# A1-MAIN.net
KiCad netlist of a schematic drawn in Altium Designer
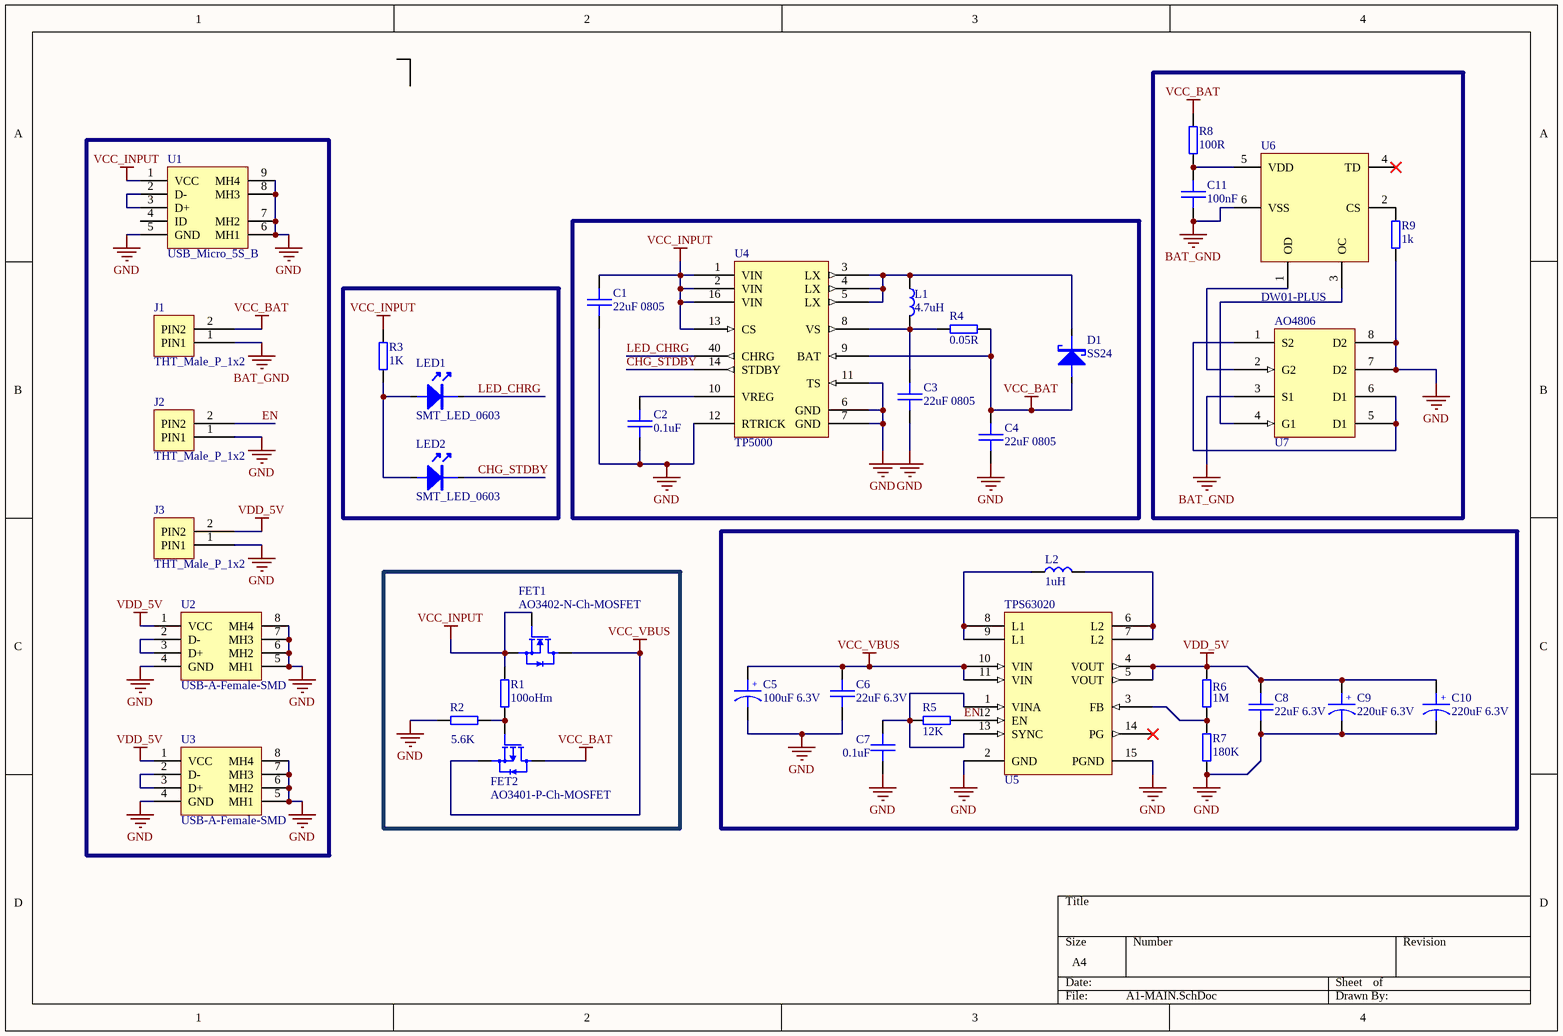
[diagram p0: A1-MAIN.SchDoc]

(export (version "E")
  (design (tool "Eeschema 10.0.6"))
  (components
    (comp (ref "AO4806") (value "U7") (footprint "SOP-8") (libsource (lib "电源管理") (part "AO4806")))
    (comp (ref "C1")
      (value "22uF 0805")
      (footprint "SMT_C_0805")
      (description "Surface mount capacitor 0805")
      (libsource (lib "Vowstar_Basic_Device") (part "SMT_C_0805"))
    )
    (comp (ref "C2")
      (value "0.1uF")
      (footprint "SMT_C_0603")
      (description "Surface mount capacitor 0603")
      (libsource (lib "Vowstar_Basic_Device") (part "SMT_C_0603"))
    )
    (comp (ref "C3")
      (value "22uF 0805")
      (footprint "SMT_C_0805")
      (description "Surface mount capacitor 0805")
      (libsource (lib "Vowstar_Basic_Device") (part "SMT_C_0805"))
    )
    (comp (ref "C4")
      (value "22uF 0805")
      (footprint "SMT_C_0805")
      (description "Surface mount capacitor 0805")
      (libsource (lib "Vowstar_Basic_Device") (part "SMT_C_0805"))
    )
    (comp (ref "C5")
      (value "100uF 6.3V")
      (footprint "SMT_C_Tantalum_A")
      (description "Capacitor, SM Tantalum; Body 3.2 x 1.6 mm (LxW typ)")
      (libsource (lib "Vowstar_Basic_Device") (part "SMT_C_Tantalum_A"))
    )
    (comp (ref "C6")
      (value "22uF 6.3V")
      (footprint "SMT_C_0805")
      (description "Surface mount capacitor 0805")
      (libsource (lib "Vowstar_Basic_Device") (part "SMT_C_0805"))
    )
    (comp (ref "C7")
      (value "0.1uF")
      (footprint "SMT_C_0603")
      (description "Surface mount capacitor 0603")
      (libsource (lib "Vowstar_Basic_Device") (part "SMT_C_0603"))
    )
    (comp (ref "C8")
      (value "22uF 6.3V")
      (footprint "SMT_C_0805")
      (description "Surface mount capacitor 0805")
      (libsource (lib "Vowstar_Basic_Device") (part "SMT_C_0805"))
    )
    (comp (ref "C9")
      (value "220uF 6.3V")
      (footprint "SMT_C_Tantalum_B")
      (description "Capacitor, SM Tantalum; Body 3.5 x 2.8 mm (LxW typ)")
      (libsource (lib "Vowstar_Basic_Device") (part "SMT_C_Tantalum_B"))
    )
    (comp (ref "C10")
      (value "220uF 6.3V")
      (footprint "SMT_C_Tantalum_B")
      (description "Capacitor, SM Tantalum; Body 3.5 x 2.8 mm (LxW typ)")
      (libsource (lib "Vowstar_Basic_Device") (part "SMT_C_Tantalum_B"))
    )
    (comp (ref "C11")
      (value "100nF")
      (footprint "SMT_C_0603")
      (description "Surface mount capacitor 0603")
      (libsource (lib "Vowstar_Basic_Device") (part "SMT_C_0603"))
    )
    (comp (ref "D1")
      (value "SS24")
      (footprint "SMT_DIODE_DO_214AC")
      (description "Surface mount schottky diode DO-214AC(SMA) Package")
      (libsource (lib "Vowstar_Basic_Device") (part "SMT_DIODE_SCHOTTKY_DO_214AC"))
    )
    (comp (ref "FET1")
      (value "AO3402-N-Ch-MOSFET")
      (footprint "AO3402-N-Ch-MOSFET")
      (description "AO3402-N-Ch,4A,30V.RDS(ON) = 0.11Ω @ VGS = 2.5V")
      (libsource (lib "Vowstar_Basic_Device") (part "AO3402-N-Ch-MOSFET"))
    )
    (comp (ref "FET2")
      (value "AO3401-P-Ch-MOSFET")
      (footprint "AO3401-P-Ch-MOSFET")
      (description "AO3401-P-Ch,-4.2A, -30V.RDS(ON) = 0.12Ω @ VGS = -2.5 V")
      (libsource (lib "Vowstar_Basic_Device") (part "AO3401-P-Ch-MOSFET"))
    )
    (comp (ref "J1")
      (value "THT_Male_P_1x2")
      (footprint "THT_Male_P_1x2-2.54mm")
      (description "THT Male pin header strip 1x2")
      (libsource (lib "Vowstar_Connector") (part "THT_Male_P_1x2"))
    )
    (comp (ref "J2")
      (value "THT_Male_P_1x2")
      (footprint "THT_Male_P_1x2-2.54mm")
      (description "THT Male pin header strip 1x2")
      (libsource (lib "Vowstar_Connector") (part "THT_Male_P_1x2"))
    )
    (comp (ref "J3")
      (value "THT_Male_P_1x2")
      (footprint "THT_Male_P_1x2-2.54mm")
      (description "THT Male pin header strip 1x2")
      (libsource (lib "Vowstar_Connector") (part "THT_Male_P_1x2"))
    )
    (comp (ref "L1")
      (value "4.7uH")
      (footprint "SMT_L_11.5mm")
      (description "Vishay HLP4040 SMT Inductor,11.5x11.5x4mm")
      (libsource (lib "Vowstar_Basic_Device") (part "SMT_L_11.5mm"))
    )
    (comp (ref "L2")
      (value "1uH")
      (footprint "SMT_L_11.5mm")
      (description "Vishay HLP4040 SMT Inductor,11.5x11.5x4mm")
      (libsource (lib "Vowstar_Basic_Device") (part "SMT_L_11.5mm"))
    )
    (comp (ref "LED1")
      (value "SMT_LED_0603")
      (footprint "SMT_LED_0603")
      (description "SMT LED")
      (libsource (lib "Vowstar_Basic_Device") (part "SMT_LED_0603"))
    )
    (comp (ref "LED2")
      (value "SMT_LED_0603")
      (footprint "SMT_LED_0603")
      (description "SMT LED")
      (libsource (lib "Vowstar_Basic_Device") (part "SMT_LED_0603"))
    )
    (comp (ref "R1")
      (value "100oHm")
      (footprint "SMT_R_0603")
      (description "Surface mount resistor 0603")
      (libsource (lib "Vowstar_Basic_Device") (part "SMT_R_0603"))
    )
    (comp (ref "R2")
      (value "5.6K")
      (footprint "SMT_R_0603")
      (description "Surface mount resistor 0603")
      (libsource (lib "Vowstar_Basic_Device") (part "SMT_R_0603"))
    )
    (comp (ref "R3")
      (value "1K")
      (footprint "SMT_R_0603")
      (description "Surface mount resistor 0603")
      (libsource (lib "Vowstar_Basic_Device") (part "SMT_R_0603"))
    )
    (comp (ref "R4")
      (value "0.05R")
      (footprint "1210")
      (description "Surface mount resistor 0805")
      (libsource (lib "Vowstar_Basic_Device") (part "SMT_R_0805"))
    )
    (comp (ref "R5")
      (value "12K")
      (footprint "SMT_R_0603")
      (description "Surface mount resistor 0603")
      (libsource (lib "Vowstar_Basic_Device") (part "SMT_R_0603"))
    )
    (comp (ref "R6")
      (value "1M")
      (footprint "SMT_R_0603")
      (description "Surface mount resistor 0603")
      (libsource (lib "Vowstar_Basic_Device") (part "SMT_R_0603"))
    )
    (comp (ref "R7")
      (value "180K")
      (footprint "SMT_R_0603")
      (description "Surface mount resistor 0603")
      (libsource (lib "Vowstar_Basic_Device") (part "SMT_R_0603"))
    )
    (comp (ref "R8")
      (value "100R")
      (footprint "SMT_R_0603")
      (description "Surface mount resistor 0603")
      (libsource (lib "Vowstar_Basic_Device") (part "SMT_R_0603"))
    )
    (comp (ref "R9")
      (value "1k")
      (footprint "SMT_R_0603")
      (description "Surface mount resistor 0603")
      (libsource (lib "Vowstar_Basic_Device") (part "SMT_R_0603"))
    )
    (comp (ref "TPS63020") (value "U5") (footprint "VSON-14") (libsource (lib "电源管理") (part "TPS63020")))
    (comp (ref "U1")
      (value "USB_Micro_5S_B")
      (footprint "USB_MICRO_5S_B")
      (description "USB micro female SMT with 4 fixed foot")
      (libsource (lib "Vowstar_Connector") (part "USB_Micro_5S_B"))
    )
    (comp (ref "U2")
      (value "USB-A-Female-SMD")
      (footprint "USB-A-SMD")
      (libsource (lib "Vowstar_Connector") (part "USB-A-Female-SMD"))
    )
    (comp (ref "U3")
      (value "USB-A-Female-SMD")
      (footprint "USB-A-SMD")
      (libsource (lib "Vowstar_Connector") (part "USB-A-Female-SMD"))
    )
    (comp (ref "U4") (value "TP5000") (footprint "QFN-16") (libsource (lib "电源管理") (part "TP5000")))
    (comp (ref "U6")
      (value "DW01-PLUS")
      (footprint "SOT23-6")
      (description "One Cell Lithium-ion/Polymer Battery Protection IC")
      (libsource (lib "Vowstar_IC_General") (part "DW01-PLUS"))
    )
  )
  (nets
    (net (code "1") (name "/CHG_STDBY") (class "Default")
      (node (ref "LED2") (pin "2") (pinfunction "K_2") (pintype "passive"))
      (node (ref "U4") (pin "14") (pinfunction "STDBY_14") (pintype "output"))
    )
    (net (code "2") (name "/EN") (class "Default")
      (node (ref "J2") (pin "2") (pinfunction "PIN2_2") (pintype "passive"))
      (node (ref "R5") (pin "2") (pinfunction "2_2") (pintype "passive"))
      (node (ref "TPS63020") (pin "12") (pinfunction "EN_12") (pintype "input"))
    )
    (net (code "3") (name "/LED_CHRG") (class "Default")
      (node (ref "LED1") (pin "2") (pinfunction "K_2") (pintype "passive"))
      (node (ref "U4") (pin "40") (pinfunction "CHRG_40") (pintype "output"))
    )
    (net (code "4") (name "BAT_GND") (class "Default")
      (node (ref "AO4806") (pin "3") (pinfunction "S1_3") (pintype "open_emitter"))
      (node (ref "C11") (pin "1") (pinfunction "1_1") (pintype "passive"))
      (node (ref "J1") (pin "1") (pinfunction "PIN1_1") (pintype "passive"))
      (node (ref "U6") (pin "6") (pinfunction "VSS_6") (pintype "passive"))
    )
    (net (code "5") (name "GND") (class "Default")
      (node (ref "AO4806") (pin "7") (pinfunction "D2_7") (pintype "open_emitter"))
      (node (ref "AO4806") (pin "8") (pinfunction "D2_8") (pintype "open_emitter"))
      (node (ref "C1") (pin "2") (pinfunction "2_2") (pintype "passive"))
      (node (ref "C10") (pin "2") (pinfunction "2_2") (pintype "passive"))
      (node (ref "C2") (pin "1") (pinfunction "1_1") (pintype "passive"))
      (node (ref "C3") (pin "2") (pinfunction "2_2") (pintype "passive"))
      (node (ref "C4") (pin "2") (pinfunction "2_2") (pintype "passive"))
      (node (ref "C5") (pin "2") (pinfunction "2_2") (pintype "passive"))
      (node (ref "C6") (pin "2") (pinfunction "2_2") (pintype "passive"))
      (node (ref "C7") (pin "2") (pinfunction "2_2") (pintype "passive"))
      (node (ref "C8") (pin "2") (pinfunction "2_2") (pintype "passive"))
      (node (ref "C9") (pin "2") (pinfunction "2_2") (pintype "passive"))
      (node (ref "J2") (pin "1") (pinfunction "PIN1_1") (pintype "passive"))
      (node (ref "J3") (pin "1") (pinfunction "PIN1_1") (pintype "passive"))
      (node (ref "R2") (pin "2") (pinfunction "2_2") (pintype "passive"))
      (node (ref "R7") (pin "1") (pinfunction "1_1") (pintype "passive"))
      (node (ref "R9") (pin "1") (pinfunction "1_1") (pintype "passive"))
      (node (ref "TPS63020") (pin "15") (pinfunction "PGND_15") (pintype "power_in"))
      (node (ref "TPS63020") (pin "2") (pinfunction "GND_2") (pintype "power_in"))
      (node (ref "U1") (pin "5") (pinfunction "GND_5") (pintype "passive"))
      (node (ref "U1") (pin "6") (pinfunction "MH1_6") (pintype "passive"))
      (node (ref "U1") (pin "7") (pinfunction "MH2_7") (pintype "passive"))
      (node (ref "U1") (pin "8") (pinfunction "MH3_8") (pintype "passive"))
      (node (ref "U1") (pin "9") (pinfunction "MH4_9") (pintype "passive"))
      (node (ref "U2") (pin "4") (pinfunction "GND_4") (pintype "passive"))
      (node (ref "U2") (pin "5") (pinfunction "MH1_5") (pintype "passive"))
      (node (ref "U2") (pin "6") (pinfunction "MH2_6") (pintype "passive"))
      (node (ref "U2") (pin "7") (pinfunction "MH3_7") (pintype "passive"))
      (node (ref "U2") (pin "8") (pinfunction "MH4_8") (pintype "passive"))
      (node (ref "U3") (pin "4") (pinfunction "GND_4") (pintype "passive"))
      (node (ref "U3") (pin "5") (pinfunction "MH1_5") (pintype "passive"))
      (node (ref "U3") (pin "6") (pinfunction "MH2_6") (pintype "passive"))
      (node (ref "U3") (pin "7") (pinfunction "MH3_7") (pintype "passive"))
      (node (ref "U3") (pin "8") (pinfunction "MH4_8") (pintype "passive"))
      (node (ref "U4") (pin "11") (pinfunction "TS_11") (pintype "input"))
      (node (ref "U4") (pin "12") (pinfunction "RTRICK_12") (pintype "passive"))
      (node (ref "U4") (pin "6") (pinfunction "GND_6") (pintype "power_in"))
      (node (ref "U4") (pin "7") (pinfunction "GND_7") (pintype "power_in"))
    )
    (net (code "6") (name "Net-(AO4806-G1)") (class "Default")
      (node (ref "AO4806") (pin "4") (pinfunction "G1_4") (pintype "input"))
      (node (ref "U6") (pin "3") (pinfunction "OC_3") (pintype "passive"))
    )
    (net (code "7") (name "Net-(AO4806-G2)") (class "Default")
      (node (ref "AO4806") (pin "2") (pinfunction "G2_2") (pintype "input"))
      (node (ref "U6") (pin "1") (pinfunction "OD_1") (pintype "passive"))
    )
    (net (code "8") (name "Net-(AO4806-S2)") (class "Default")
      (node (ref "AO4806") (pin "1") (pinfunction "S2_1") (pintype "open_emitter"))
      (node (ref "AO4806") (pin "5") (pinfunction "D1_5") (pintype "open_emitter"))
      (node (ref "AO4806") (pin "6") (pinfunction "D1_6") (pintype "open_emitter"))
    )
    (net (code "9") (name "Net-(D1-K)") (class "Default")
      (node (ref "D1") (pin "2") (pinfunction "K_2") (pintype "passive"))
      (node (ref "L1") (pin "2") (pinfunction "2_2") (pintype "passive"))
      (node (ref "U4") (pin "3") (pinfunction "LX_3") (pintype "output"))
      (node (ref "U4") (pin "4") (pinfunction "LX_4") (pintype "output"))
      (node (ref "U4") (pin "5") (pinfunction "LX_5") (pintype "output"))
    )
    (net (code "10") (name "Net-(FET2-G)") (class "Default")
      (node (ref "FET2") (pin "1") (pinfunction "G_1") (pintype "passive"))
      (node (ref "R1") (pin "2") (pinfunction "2_2") (pintype "passive"))
      (node (ref "R2") (pin "1") (pinfunction "1_1") (pintype "passive"))
    )
    (net (code "11") (name "Net-(L2-Pad1)") (class "Default")
      (node (ref "L2") (pin "1") (pinfunction "1_1") (pintype "passive"))
      (node (ref "TPS63020") (pin "6") (pinfunction "L2_6") (pintype "passive"))
      (node (ref "TPS63020") (pin "7") (pinfunction "L2_7") (pintype "passive"))
    )
    (net (code "12") (name "Net-(L2-Pad2)") (class "Default")
      (node (ref "L2") (pin "2") (pinfunction "2_2") (pintype "passive"))
      (node (ref "TPS63020") (pin "8") (pinfunction "L1_8") (pintype "passive"))
      (node (ref "TPS63020") (pin "9") (pinfunction "L1_9") (pintype "passive"))
    )
    (net (code "13") (name "Net-(LED1-A)") (class "Default")
      (node (ref "LED1") (pin "1") (pinfunction "A_1") (pintype "passive"))
      (node (ref "LED2") (pin "1") (pinfunction "A_1") (pintype "passive"))
      (node (ref "R3") (pin "1") (pinfunction "1_1") (pintype "passive"))
    )
    (net (code "14") (name "Net-(TPS63020-FB)") (class "Default")
      (node (ref "R6") (pin "1") (pinfunction "1_1") (pintype "passive"))
      (node (ref "R7") (pin "2") (pinfunction "2_2") (pintype "passive"))
      (node (ref "TPS63020") (pin "3") (pinfunction "FB_3") (pintype "input"))
    )
    (net (code "15") (name "Net-(TPS63020-SYNC)") (class "Default")
      (node (ref "C7") (pin "1") (pinfunction "1_1") (pintype "passive"))
      (node (ref "R5") (pin "1") (pinfunction "1_1") (pintype "passive"))
      (node (ref "TPS63020") (pin "1") (pinfunction "VINA_1") (pintype "input"))
      (node (ref "TPS63020") (pin "13") (pinfunction "SYNC_13") (pintype "input"))
    )
    (net (code "16") (name "Net-(U1-D+)") (class "Default")
      (node (ref "U1") (pin "2") (pinfunction "D-_2") (pintype "passive"))
      (node (ref "U1") (pin "3") (pinfunction "D+_3") (pintype "passive"))
    )
    (net (code "17") (name "Net-(U2-D+)") (class "Default")
      (node (ref "U2") (pin "2") (pinfunction "D-_2") (pintype "passive"))
      (node (ref "U2") (pin "3") (pinfunction "D+_3") (pintype "passive"))
    )
    (net (code "18") (name "Net-(U3-D+)") (class "Default")
      (node (ref "U3") (pin "2") (pinfunction "D-_2") (pintype "passive"))
      (node (ref "U3") (pin "3") (pinfunction "D+_3") (pintype "passive"))
    )
    (net (code "19") (name "Net-(U4-VREG)") (class "Default")
      (node (ref "C2") (pin "2") (pinfunction "2_2") (pintype "passive"))
      (node (ref "U4") (pin "10") (pinfunction "VREG_10") (pintype "passive"))
    )
    (net (code "20") (name "Net-(U4-VS)") (class "Default")
      (node (ref "C3") (pin "1") (pinfunction "1_1") (pintype "passive"))
      (node (ref "L1") (pin "1") (pinfunction "1_1") (pintype "passive"))
      (node (ref "R4") (pin "2") (pinfunction "2_2") (pintype "passive"))
      (node (ref "U4") (pin "8") (pinfunction "VS_8") (pintype "output"))
    )
    (net (code "21") (name "Net-(U6-CS)") (class "Default")
      (node (ref "R9") (pin "2") (pinfunction "2_2") (pintype "passive"))
      (node (ref "U6") (pin "2") (pinfunction "CS_2") (pintype "passive"))
    )
    (net (code "22") (name "Net-(U6-VDD)") (class "Default")
      (node (ref "C11") (pin "2") (pinfunction "2_2") (pintype "passive"))
      (node (ref "R8") (pin "2") (pinfunction "2_2") (pintype "passive"))
      (node (ref "U6") (pin "5") (pinfunction "VDD_5") (pintype "passive"))
    )
    (net (code "23") (name "VCC_BAT") (class "Default")
      (node (ref "C4") (pin "1") (pinfunction "1_1") (pintype "passive"))
      (node (ref "D1") (pin "1") (pinfunction "A_1") (pintype "passive"))
      (node (ref "FET2") (pin "3") (pinfunction "D_3") (pintype "passive"))
      (node (ref "J1") (pin "2") (pinfunction "PIN2_2") (pintype "passive"))
      (node (ref "R4") (pin "1") (pinfunction "1_1") (pintype "passive"))
      (node (ref "R8") (pin "1") (pinfunction "1_1") (pintype "passive"))
      (node (ref "U4") (pin "9") (pinfunction "BAT_9") (pintype "input"))
    )
    (net (code "24") (name "VCC_INPUT") (class "Default")
      (node (ref "C1") (pin "1") (pinfunction "1_1") (pintype "passive"))
      (node (ref "FET1") (pin "1") (pinfunction "G_1") (pintype "passive"))
      (node (ref "FET1") (pin "2") (pinfunction "S_2") (pintype "passive"))
      (node (ref "R1") (pin "1") (pinfunction "1_1") (pintype "passive"))
      (node (ref "R3") (pin "2") (pinfunction "2_2") (pintype "passive"))
      (node (ref "U1") (pin "1") (pinfunction "VCC_1") (pintype "passive"))
      (node (ref "U4") (pin "1") (pinfunction "VIN_1") (pintype "power_in"))
      (node (ref "U4") (pin "13") (pinfunction "CS_13") (pintype "input"))
      (node (ref "U4") (pin "16") (pinfunction "VIN_16") (pintype "power_in"))
      (node (ref "U4") (pin "2") (pinfunction "VIN_2") (pintype "power_in"))
    )
    (net (code "25") (name "VCC_VBUS") (class "Default")
      (node (ref "C5") (pin "1") (pinfunction "1_1") (pintype "passive"))
      (node (ref "C6") (pin "1") (pinfunction "1_1") (pintype "passive"))
      (node (ref "FET1") (pin "3") (pinfunction "D_3") (pintype "passive"))
      (node (ref "FET2") (pin "2") (pinfunction "S_2") (pintype "passive"))
      (node (ref "TPS63020") (pin "10") (pinfunction "VIN_10") (pintype "input"))
      (node (ref "TPS63020") (pin "11") (pinfunction "VIN_11") (pintype "input"))
    )
    (net (code "26") (name "VDD_5V") (class "Default")
      (node (ref "C10") (pin "1") (pinfunction "1_1") (pintype "passive"))
      (node (ref "C8") (pin "1") (pinfunction "1_1") (pintype "passive"))
      (node (ref "C9") (pin "1") (pinfunction "1_1") (pintype "passive"))
      (node (ref "J3") (pin "2") (pinfunction "PIN2_2") (pintype "passive"))
      (node (ref "R6") (pin "2") (pinfunction "2_2") (pintype "passive"))
      (node (ref "TPS63020") (pin "4") (pinfunction "VOUT_4") (pintype "output"))
      (node (ref "TPS63020") (pin "5") (pinfunction "VOUT_5") (pintype "output"))
      (node (ref "U2") (pin "1") (pinfunction "VCC_1") (pintype "passive"))
      (node (ref "U3") (pin "1") (pinfunction "VCC_1") (pintype "passive"))
    )
    (net (code "27") (name "unconnected-(TPS63020-PG-Pad14)") (class "Default")
      (node (ref "TPS63020") (pin "14") (pinfunction "PG_14") (pintype "output+no_connect"))
    )
    (net (code "28") (name "unconnected-(U1-ID-Pad4)") (class "Default")
      (node (ref "U1") (pin "4") (pinfunction "ID_4") (pintype "passive"))
    )
    (net (code "29") (name "unconnected-(U6-TD-Pad4)") (class "Default")
      (node (ref "U6") (pin "4") (pinfunction "TD_4") (pintype "passive+no_connect"))
    )
  )
)
